# SwitchBoard_MP3_8.net
KiCad netlist of a schematic drawn in EAGLE
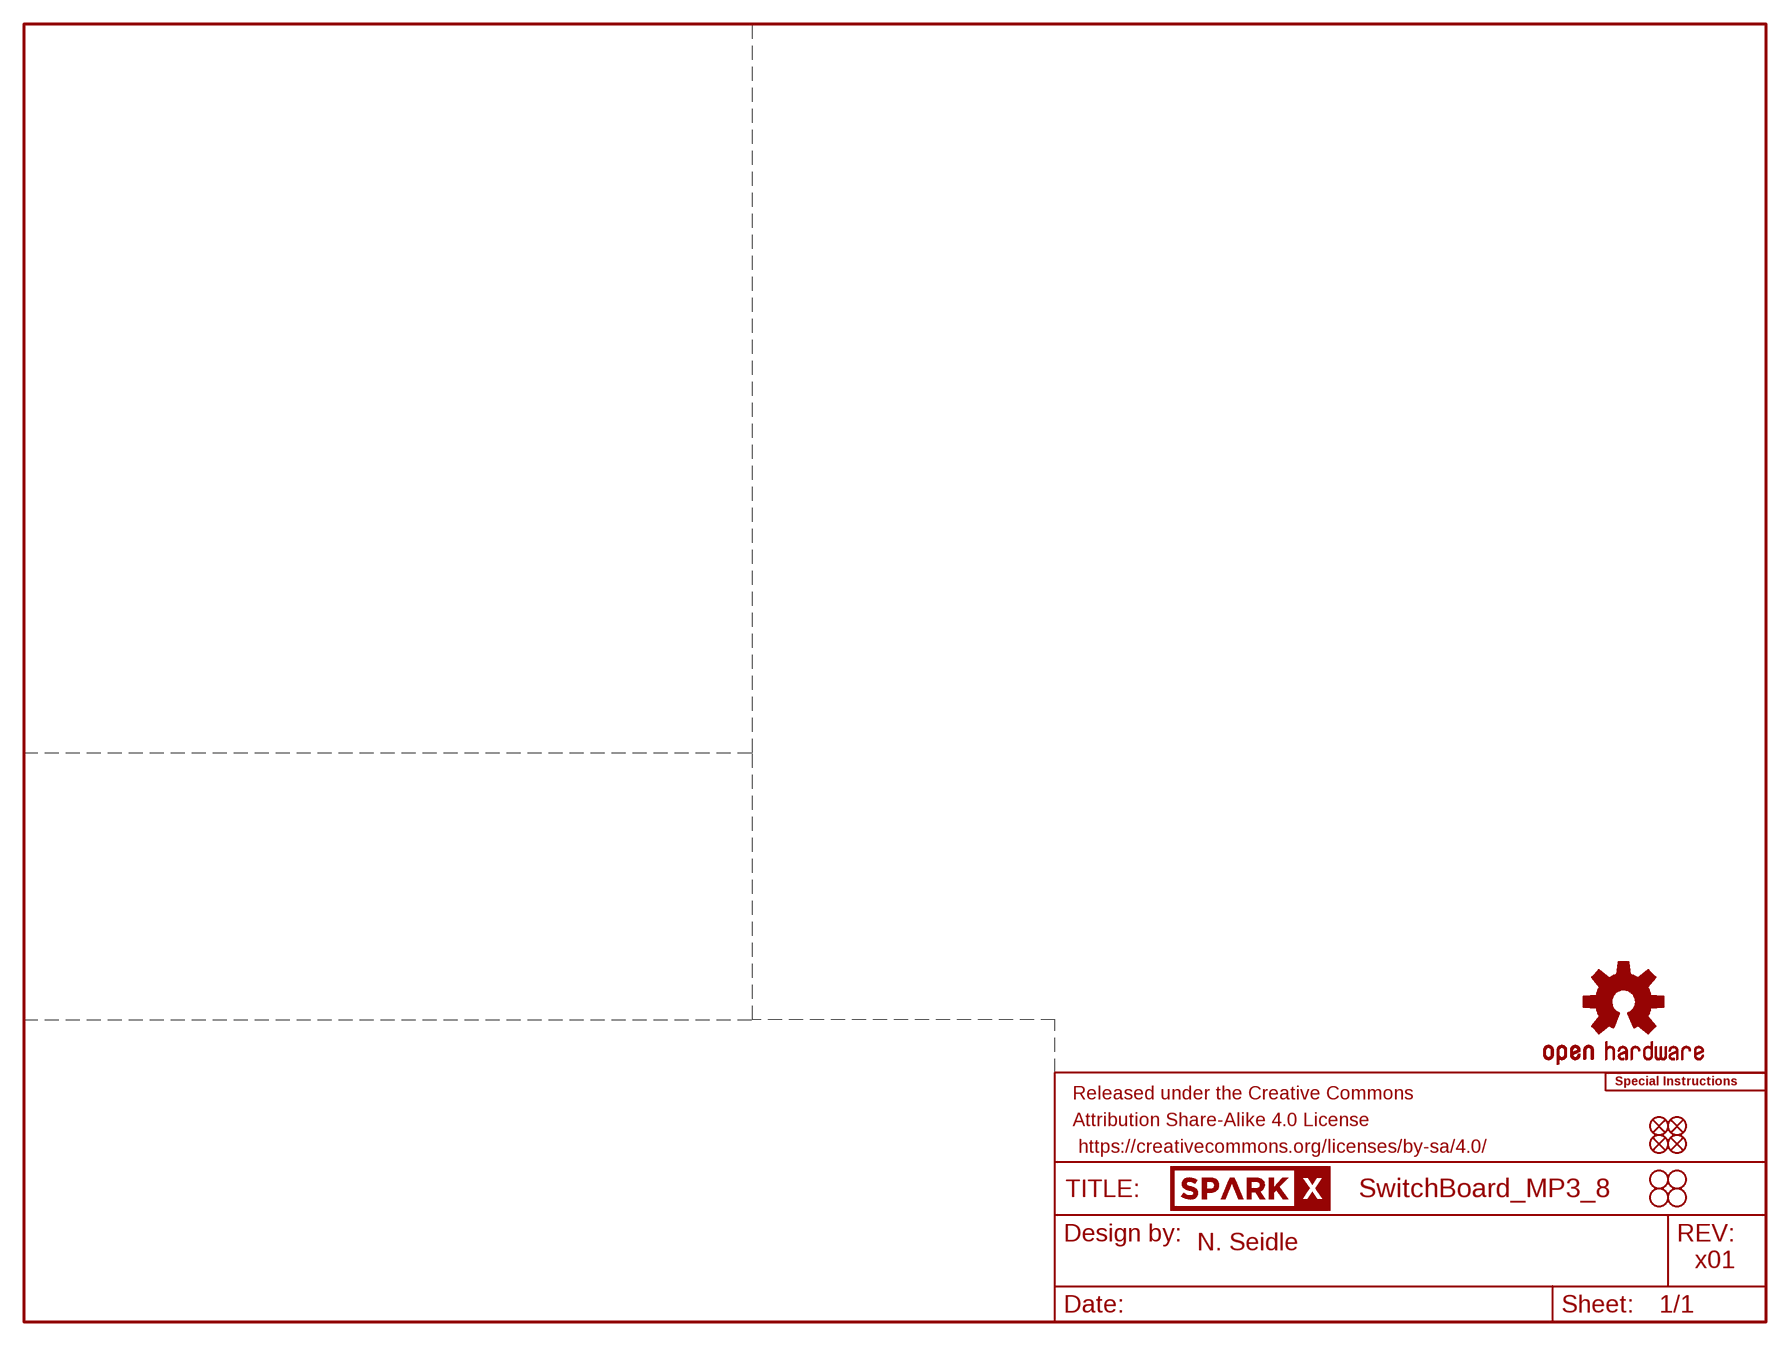
[diagram p0: schematic, sheet 1, part 1 of 2]
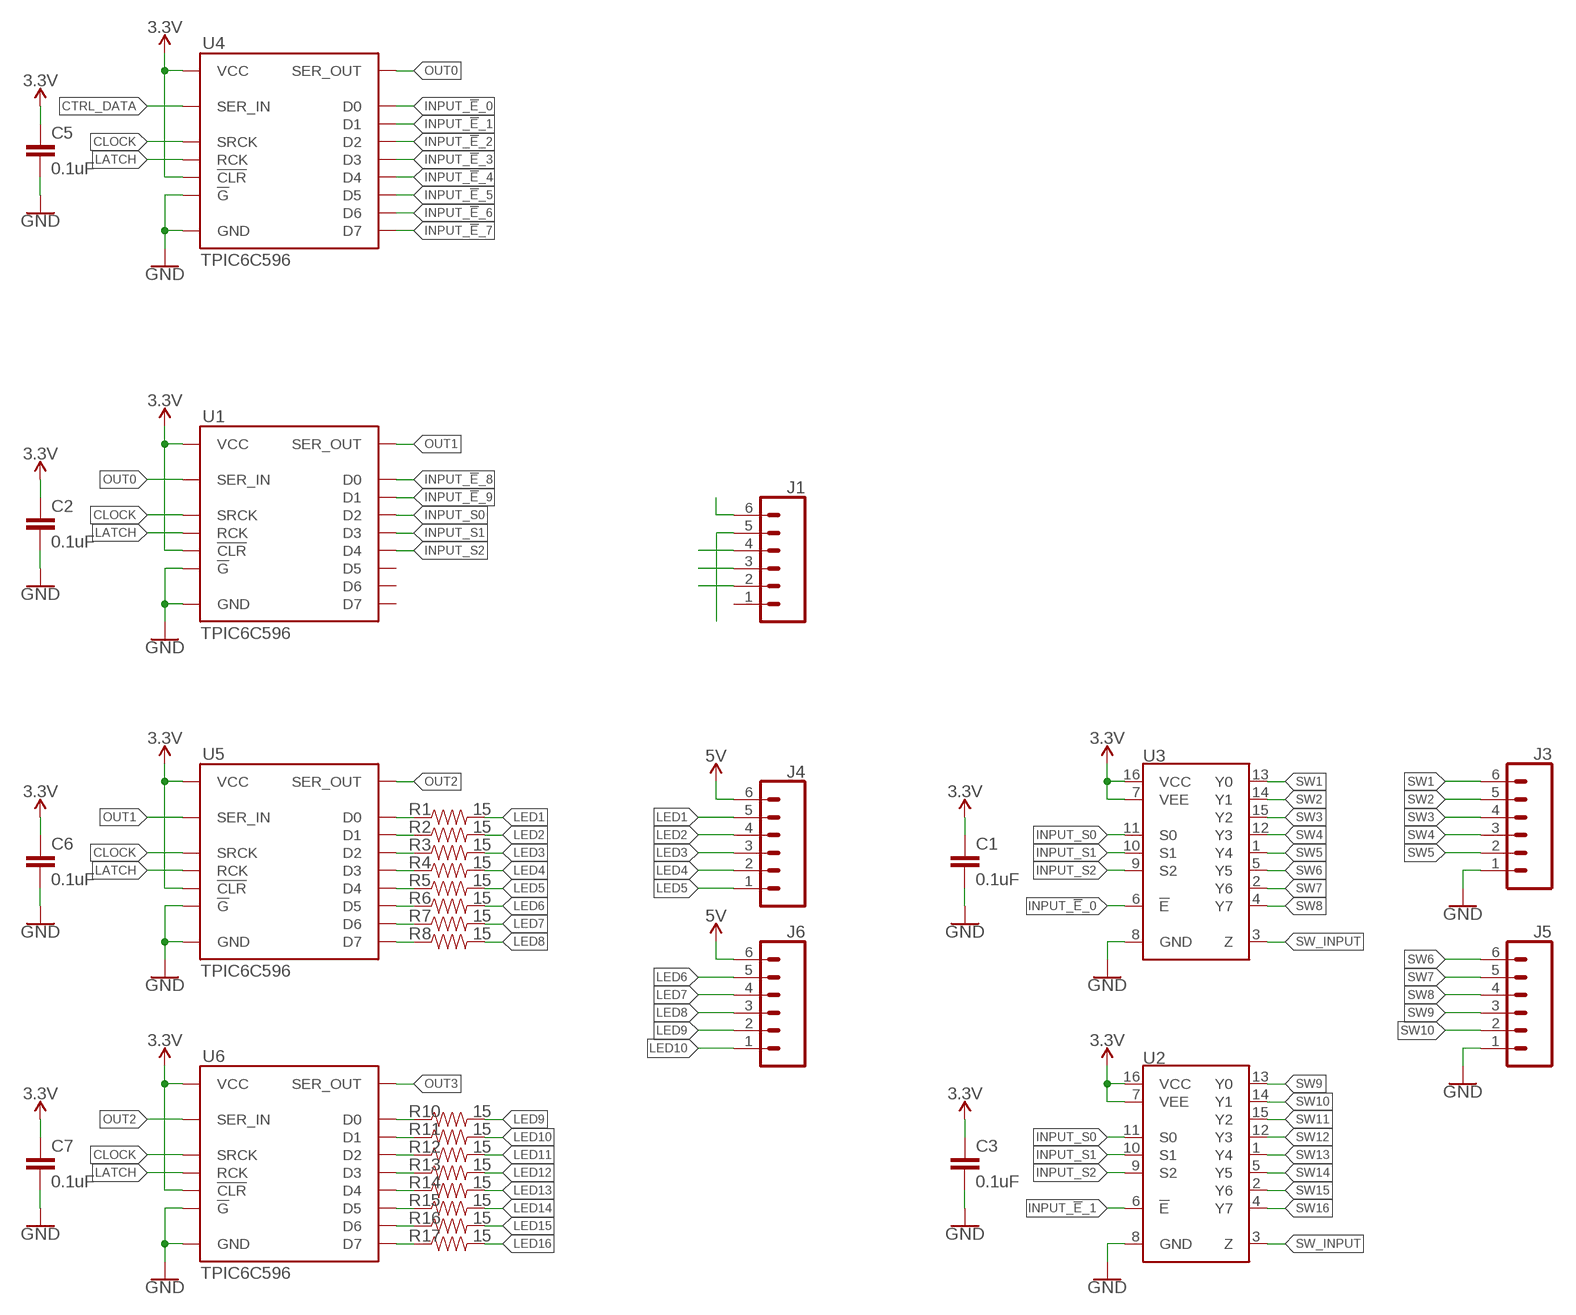
[diagram p1: schematic, sheet 1, part 2 of 2]

(export (version "E")
  (design (tool "Eeschema 10.0.6"))
  (components
    (comp (ref "C1")
      (value "0.1uF")
      (footprint "eagle-import:0603")
      (libsource (lib "eagle-import") (part "0.1UF-0603-25V-10%-X7R-WE"))
    )
    (comp (ref "C2")
      (value "0.1uF")
      (footprint "eagle-import:0603")
      (libsource (lib "eagle-import") (part "0.1UF-0603-25V-10%-X7R-WE"))
    )
    (comp (ref "C3")
      (value "0.1uF")
      (footprint "eagle-import:0603")
      (libsource (lib "eagle-import") (part "0.1UF-0603-25V-10%-X7R-WE"))
    )
    (comp (ref "C5")
      (value "0.1uF")
      (footprint "eagle-import:0603")
      (libsource (lib "eagle-import") (part "0.1UF-0603-25V-10%-X7R-WE"))
    )
    (comp (ref "C6")
      (value "0.1uF")
      (footprint "eagle-import:0603")
      (libsource (lib "eagle-import") (part "0.1UF-0603-25V-10%-X7R-WE"))
    )
    (comp (ref "C7")
      (value "0.1uF")
      (footprint "eagle-import:0603")
      (libsource (lib "eagle-import") (part "0.1UF-0603-25V-10%-X7R-WE"))
    )
    (comp (ref "FD1")
      (value "FIDUCIAL1X2")
      (footprint "eagle-import:FIDUCIAL-1X2")
      (libsource (lib "eagle-import") (part "FIDUCIAL1X2"))
    )
    (comp (ref "FD2")
      (value "FIDUCIAL1X2")
      (footprint "eagle-import:FIDUCIAL-1X2")
      (libsource (lib "eagle-import") (part "FIDUCIAL1X2"))
    )
    (comp (ref "FD3")
      (value "FIDUCIAL1X2")
      (footprint "eagle-import:FIDUCIAL-1X2")
      (libsource (lib "eagle-import") (part "FIDUCIAL1X2"))
    )
    (comp (ref "FD4")
      (value "FIDUCIAL1X2")
      (footprint "eagle-import:FIDUCIAL-1X2")
      (libsource (lib "eagle-import") (part "FIDUCIAL1X2"))
    )
    (comp (ref "FRAME1")
      (value "FRAME-LETTER")
      (footprint "eagle-import:CREATIVE_COMMONS")
      (libsource (lib "eagle-import") (part "FRAME-LETTER"))
    )
    (comp (ref "H1")
      (value "STAND-OFF")
      (footprint "eagle-import:STAND-OFF")
      (libsource (lib "eagle-import") (part "STAND-OFF"))
    )
    (comp (ref "H2")
      (value "STAND-OFF")
      (footprint "eagle-import:STAND-OFF")
      (libsource (lib "eagle-import") (part "STAND-OFF"))
    )
    (comp (ref "H3")
      (value "STAND-OFF")
      (footprint "eagle-import:STAND-OFF")
      (libsource (lib "eagle-import") (part "STAND-OFF"))
    )
    (comp (ref "H4")
      (value "STAND-OFF")
      (footprint "eagle-import:STAND-OFF")
      (libsource (lib "eagle-import") (part "STAND-OFF"))
    )
    (comp (ref "J1")
      (value "CONN_06JST-SMD-LOCKING")
      (footprint "eagle-import:JST-6-SMD-1.25MM-LOCKING")
      (libsource (lib "eagle-import") (part "CONN_06JST-SMD-LOCKING"))
    )
    (comp (ref "J3")
      (value "CONN_06JST-SMD-LOCKING")
      (footprint "eagle-import:JST-6-SMD-1.25MM-LOCKING")
      (libsource (lib "eagle-import") (part "CONN_06JST-SMD-LOCKING"))
    )
    (comp (ref "J4")
      (value "CONN_06JST-SMD-LOCKING")
      (footprint "eagle-import:JST-6-SMD-1.25MM-LOCKING")
      (libsource (lib "eagle-import") (part "CONN_06JST-SMD-LOCKING"))
    )
    (comp (ref "J5")
      (value "CONN_06JST-SMD-LOCKING")
      (footprint "eagle-import:JST-6-SMD-1.25MM-LOCKING")
      (libsource (lib "eagle-import") (part "CONN_06JST-SMD-LOCKING"))
    )
    (comp (ref "J6")
      (value "CONN_06JST-SMD-LOCKING")
      (footprint "eagle-import:JST-6-SMD-1.25MM-LOCKING")
      (libsource (lib "eagle-import") (part "CONN_06JST-SMD-LOCKING"))
    )
    (comp (ref "LOGO1")
      (value "SPECIAL_INSTRUCTIONS-ORDERING")
      (footprint "eagle-import:ORDERING_INSTRUCTIONS")
      (libsource (lib "eagle-import") (part "SPECIAL_INSTRUCTIONS-ORDERING"))
    )
    (comp (ref "LOGO2")
      (value "OSHW-LOGOS")
      (footprint "eagle-import:OSHW-LOGO-S")
      (libsource (lib "eagle-import") (part "OSHW-LOGOS"))
    )
    (comp (ref "R1")
      (value "15")
      (footprint "eagle-import:0603")
      (libsource (lib "eagle-import") (part "15OHM-0603-1/10W-1%"))
    )
    (comp (ref "R2")
      (value "15")
      (footprint "eagle-import:0603")
      (libsource (lib "eagle-import") (part "15OHM-0603-1/10W-1%"))
    )
    (comp (ref "R3")
      (value "15")
      (footprint "eagle-import:0603")
      (libsource (lib "eagle-import") (part "15OHM-0603-1/10W-1%"))
    )
    (comp (ref "R4")
      (value "15")
      (footprint "eagle-import:0603")
      (libsource (lib "eagle-import") (part "15OHM-0603-1/10W-1%"))
    )
    (comp (ref "R5")
      (value "15")
      (footprint "eagle-import:0603")
      (libsource (lib "eagle-import") (part "15OHM-0603-1/10W-1%"))
    )
    (comp (ref "R6")
      (value "15")
      (footprint "eagle-import:0603")
      (libsource (lib "eagle-import") (part "15OHM-0603-1/10W-1%"))
    )
    (comp (ref "R7")
      (value "15")
      (footprint "eagle-import:0603")
      (libsource (lib "eagle-import") (part "15OHM-0603-1/10W-1%"))
    )
    (comp (ref "R8")
      (value "15")
      (footprint "eagle-import:0603")
      (libsource (lib "eagle-import") (part "15OHM-0603-1/10W-1%"))
    )
    (comp (ref "R10")
      (value "15")
      (footprint "eagle-import:0603")
      (libsource (lib "eagle-import") (part "15OHM-0603-1/10W-1%"))
    )
    (comp (ref "R11")
      (value "15")
      (footprint "eagle-import:0603")
      (libsource (lib "eagle-import") (part "15OHM-0603-1/10W-1%"))
    )
    (comp (ref "R12")
      (value "15")
      (footprint "eagle-import:0603")
      (libsource (lib "eagle-import") (part "15OHM-0603-1/10W-1%"))
    )
    (comp (ref "R13")
      (value "15")
      (footprint "eagle-import:0603")
      (libsource (lib "eagle-import") (part "15OHM-0603-1/10W-1%"))
    )
    (comp (ref "R14")
      (value "15")
      (footprint "eagle-import:0603")
      (libsource (lib "eagle-import") (part "15OHM-0603-1/10W-1%"))
    )
    (comp (ref "R15")
      (value "15")
      (footprint "eagle-import:0603")
      (libsource (lib "eagle-import") (part "15OHM-0603-1/10W-1%"))
    )
    (comp (ref "R16")
      (value "15")
      (footprint "eagle-import:0603")
      (libsource (lib "eagle-import") (part "15OHM-0603-1/10W-1%"))
    )
    (comp (ref "R17")
      (value "15")
      (footprint "eagle-import:0603")
      (libsource (lib "eagle-import") (part "15OHM-0603-1/10W-1%"))
    )
    (comp (ref "U$1")
      (value "SPARKX-LOGO4")
      (footprint "eagle-import:SPARKX-MEDIUM")
      (libsource (lib "eagle-import") (part "SPARKX-LOGO4"))
    )
    (comp (ref "U1")
      (value "TPIC6C596")
      (footprint "eagle-import:SO016")
      (libsource (lib "eagle-import") (part "TPIC6C596SOIC"))
    )
    (comp (ref "U2")
      (value "744051")
      (footprint "eagle-import:SO16")
      (libsource (lib "eagle-import") (part "744051"))
    )
    (comp (ref "U3")
      (value "744051")
      (footprint "eagle-import:SO16")
      (libsource (lib "eagle-import") (part "744051"))
    )
    (comp (ref "U4")
      (value "TPIC6C596")
      (footprint "eagle-import:SO016")
      (libsource (lib "eagle-import") (part "TPIC6C596SOIC"))
    )
    (comp (ref "U5")
      (value "TPIC6C596")
      (footprint "eagle-import:SO016")
      (libsource (lib "eagle-import") (part "TPIC6C596SOIC"))
    )
    (comp (ref "U6")
      (value "TPIC6C596")
      (footprint "eagle-import:SO016")
      (libsource (lib "eagle-import") (part "TPIC6C596SOIC"))
    )
  )
  (nets
    (net (code "1") (name "/INPUT_~{E}_0") (class "Default")
      (node (ref "U3") (pin "6") (pinfunction "~{E}_6") (pintype "bidirectional"))
      (node (ref "U4") (pin "3") (pinfunction "D0_3") (pintype "output"))
    )
    (net (code "2") (name "/INPUT_~{E}_1") (class "Default")
      (node (ref "U2") (pin "6") (pinfunction "~{E}_6") (pintype "bidirectional"))
      (node (ref "U4") (pin "4") (pinfunction "D1_4") (pintype "output"))
    )
    (net (code "3") (name "/INPUT_~{E}_2") (class "Default")
      (node (ref "U4") (pin "5") (pinfunction "D2_5") (pintype "output"))
    )
    (net (code "4") (name "/INPUT_~{E}_3") (class "Default")
      (node (ref "U4") (pin "6") (pinfunction "D3_6") (pintype "output"))
    )
    (net (code "5") (name "/INPUT_~{E}_4") (class "Default")
      (node (ref "U4") (pin "11") (pinfunction "D4_11") (pintype "output"))
    )
    (net (code "6") (name "/INPUT_~{E}_5") (class "Default")
      (node (ref "U4") (pin "12") (pinfunction "D5_12") (pintype "output"))
    )
    (net (code "7") (name "/INPUT_~{E}_6") (class "Default")
      (node (ref "U4") (pin "13") (pinfunction "D6_13") (pintype "output"))
    )
    (net (code "8") (name "/INPUT_~{E}_7") (class "Default")
      (node (ref "U4") (pin "14") (pinfunction "D7_14") (pintype "output"))
    )
    (net (code "9") (name "/INPUT_~{E}_8") (class "Default")
      (node (ref "U1") (pin "3") (pinfunction "D0_3") (pintype "output"))
    )
    (net (code "10") (name "/INPUT_~{E}_9") (class "Default")
      (node (ref "U1") (pin "4") (pinfunction "D1_4") (pintype "output"))
    )
    (net (code "11") (name "3.3V") (class "Default")
      (node (ref "C1") (pin "1") (pinfunction "1_1") (pintype "passive"))
      (node (ref "C2") (pin "1") (pinfunction "1_1") (pintype "passive"))
      (node (ref "C3") (pin "1") (pinfunction "1_1") (pintype "passive"))
      (node (ref "C5") (pin "1") (pinfunction "1_1") (pintype "passive"))
      (node (ref "C6") (pin "1") (pinfunction "1_1") (pintype "passive"))
      (node (ref "C7") (pin "1") (pinfunction "1_1") (pintype "passive"))
      (node (ref "U1") (pin "1") (pinfunction "VCC_1") (pintype "power_in"))
      (node (ref "U1") (pin "7") (pinfunction "~{CLR}_7") (pintype "input"))
      (node (ref "U2") (pin "16") (pinfunction "VCC_16") (pintype "bidirectional"))
      (node (ref "U2") (pin "7") (pinfunction "VEE_7") (pintype "bidirectional"))
      (node (ref "U3") (pin "16") (pinfunction "VCC_16") (pintype "bidirectional"))
      (node (ref "U3") (pin "7") (pinfunction "VEE_7") (pintype "bidirectional"))
      (node (ref "U4") (pin "1") (pinfunction "VCC_1") (pintype "power_in"))
      (node (ref "U4") (pin "7") (pinfunction "~{CLR}_7") (pintype "input"))
      (node (ref "U5") (pin "1") (pinfunction "VCC_1") (pintype "power_in"))
      (node (ref "U5") (pin "7") (pinfunction "~{CLR}_7") (pintype "input"))
      (node (ref "U6") (pin "1") (pinfunction "VCC_1") (pintype "power_in"))
      (node (ref "U6") (pin "7") (pinfunction "~{CLR}_7") (pintype "input"))
    )
    (net (code "12") (name "5V") (class "Default")
      (node (ref "J4") (pin "6") (pinfunction "6_6") (pintype "passive"))
      (node (ref "J6") (pin "6") (pinfunction "6_6") (pintype "passive"))
    )
    (net (code "13") (name "CLOCK") (class "Default")
      (node (ref "U1") (pin "15") (pinfunction "SRCK_15") (pintype "input"))
      (node (ref "U4") (pin "15") (pinfunction "SRCK_15") (pintype "input"))
      (node (ref "U5") (pin "15") (pinfunction "SRCK_15") (pintype "input"))
      (node (ref "U6") (pin "15") (pinfunction "SRCK_15") (pintype "input"))
    )
    (net (code "14") (name "CTRL_DATA") (class "Default")
      (node (ref "U4") (pin "2") (pinfunction "SER_IN_2") (pintype "input"))
    )
    (net (code "15") (name "GND") (class "Default")
      (node (ref "C1") (pin "2") (pinfunction "2_2") (pintype "passive"))
      (node (ref "C2") (pin "2") (pinfunction "2_2") (pintype "passive"))
      (node (ref "C3") (pin "2") (pinfunction "2_2") (pintype "passive"))
      (node (ref "C5") (pin "2") (pinfunction "2_2") (pintype "passive"))
      (node (ref "C6") (pin "2") (pinfunction "2_2") (pintype "passive"))
      (node (ref "C7") (pin "2") (pinfunction "2_2") (pintype "passive"))
      (node (ref "J3") (pin "1") (pinfunction "1_1") (pintype "passive"))
      (node (ref "J5") (pin "1") (pinfunction "1_1") (pintype "passive"))
      (node (ref "U1") (pin "16") (pinfunction "GND_16") (pintype "power_in"))
      (node (ref "U1") (pin "8") (pinfunction "~{G}_8") (pintype "input"))
      (node (ref "U2") (pin "8") (pinfunction "GND_8") (pintype "bidirectional"))
      (node (ref "U3") (pin "8") (pinfunction "GND_8") (pintype "bidirectional"))
      (node (ref "U4") (pin "16") (pinfunction "GND_16") (pintype "power_in"))
      (node (ref "U4") (pin "8") (pinfunction "~{G}_8") (pintype "input"))
      (node (ref "U5") (pin "16") (pinfunction "GND_16") (pintype "power_in"))
      (node (ref "U5") (pin "8") (pinfunction "~{G}_8") (pintype "input"))
      (node (ref "U6") (pin "16") (pinfunction "GND_16") (pintype "power_in"))
      (node (ref "U6") (pin "8") (pinfunction "~{G}_8") (pintype "input"))
    )
    (net (code "16") (name "INPUT_S0") (class "Default")
      (node (ref "U1") (pin "5") (pinfunction "D2_5") (pintype "output"))
      (node (ref "U2") (pin "11") (pinfunction "S0_11") (pintype "bidirectional"))
      (node (ref "U3") (pin "11") (pinfunction "S0_11") (pintype "bidirectional"))
    )
    (net (code "17") (name "INPUT_S1") (class "Default")
      (node (ref "U1") (pin "6") (pinfunction "D3_6") (pintype "output"))
      (node (ref "U2") (pin "10") (pinfunction "S1_10") (pintype "bidirectional"))
      (node (ref "U3") (pin "10") (pinfunction "S1_10") (pintype "bidirectional"))
    )
    (net (code "18") (name "INPUT_S2") (class "Default")
      (node (ref "U1") (pin "11") (pinfunction "D4_11") (pintype "output"))
      (node (ref "U2") (pin "9") (pinfunction "S2_9") (pintype "bidirectional"))
      (node (ref "U3") (pin "9") (pinfunction "S2_9") (pintype "bidirectional"))
    )
    (net (code "19") (name "LATCH") (class "Default")
      (node (ref "U1") (pin "10") (pinfunction "RCK_10") (pintype "input"))
      (node (ref "U4") (pin "10") (pinfunction "RCK_10") (pintype "input"))
      (node (ref "U5") (pin "10") (pinfunction "RCK_10") (pintype "input"))
      (node (ref "U6") (pin "10") (pinfunction "RCK_10") (pintype "input"))
    )
    (net (code "20") (name "LED1") (class "Default")
      (node (ref "J4") (pin "5") (pinfunction "5_5") (pintype "passive"))
      (node (ref "R1") (pin "2") (pinfunction "2_2") (pintype "passive"))
    )
    (net (code "21") (name "LED2") (class "Default")
      (node (ref "J4") (pin "4") (pinfunction "4_4") (pintype "passive"))
      (node (ref "R2") (pin "2") (pinfunction "2_2") (pintype "passive"))
    )
    (net (code "22") (name "LED3") (class "Default")
      (node (ref "J4") (pin "3") (pinfunction "3_3") (pintype "passive"))
      (node (ref "R3") (pin "2") (pinfunction "2_2") (pintype "passive"))
    )
    (net (code "23") (name "LED4") (class "Default")
      (node (ref "J4") (pin "2") (pinfunction "2_2") (pintype "passive"))
      (node (ref "R4") (pin "2") (pinfunction "2_2") (pintype "passive"))
    )
    (net (code "24") (name "LED5") (class "Default")
      (node (ref "J4") (pin "1") (pinfunction "1_1") (pintype "passive"))
      (node (ref "R5") (pin "2") (pinfunction "2_2") (pintype "passive"))
    )
    (net (code "25") (name "LED6") (class "Default")
      (node (ref "J6") (pin "5") (pinfunction "5_5") (pintype "passive"))
      (node (ref "R6") (pin "2") (pinfunction "2_2") (pintype "passive"))
    )
    (net (code "26") (name "LED7") (class "Default")
      (node (ref "J6") (pin "4") (pinfunction "4_4") (pintype "passive"))
      (node (ref "R7") (pin "2") (pinfunction "2_2") (pintype "passive"))
    )
    (net (code "27") (name "LED8") (class "Default")
      (node (ref "J6") (pin "3") (pinfunction "3_3") (pintype "passive"))
      (node (ref "R8") (pin "2") (pinfunction "2_2") (pintype "passive"))
    )
    (net (code "28") (name "LED9") (class "Default")
      (node (ref "J6") (pin "2") (pinfunction "2_2") (pintype "passive"))
      (node (ref "R10") (pin "2") (pinfunction "2_2") (pintype "passive"))
    )
    (net (code "29") (name "LED10") (class "Default")
      (node (ref "J6") (pin "1") (pinfunction "1_1") (pintype "passive"))
      (node (ref "R11") (pin "2") (pinfunction "2_2") (pintype "passive"))
    )
    (net (code "30") (name "LED11") (class "Default")
      (node (ref "R12") (pin "2") (pinfunction "2_2") (pintype "passive"))
    )
    (net (code "31") (name "LED12") (class "Default")
      (node (ref "R13") (pin "2") (pinfunction "2_2") (pintype "passive"))
    )
    (net (code "32") (name "LED13") (class "Default")
      (node (ref "R14") (pin "2") (pinfunction "2_2") (pintype "passive"))
    )
    (net (code "33") (name "LED14") (class "Default")
      (node (ref "R15") (pin "2") (pinfunction "2_2") (pintype "passive"))
    )
    (net (code "34") (name "LED15") (class "Default")
      (node (ref "R16") (pin "2") (pinfunction "2_2") (pintype "passive"))
    )
    (net (code "35") (name "LED16") (class "Default")
      (node (ref "R17") (pin "2") (pinfunction "2_2") (pintype "passive"))
    )
    (net (code "36") (name "Net-(U5-D0)") (class "Default")
      (node (ref "R1") (pin "1") (pinfunction "1_1") (pintype "passive"))
      (node (ref "U5") (pin "3") (pinfunction "D0_3") (pintype "output"))
    )
    (net (code "37") (name "Net-(U5-D1)") (class "Default")
      (node (ref "R2") (pin "1") (pinfunction "1_1") (pintype "passive"))
      (node (ref "U5") (pin "4") (pinfunction "D1_4") (pintype "output"))
    )
    (net (code "38") (name "Net-(U5-D2)") (class "Default")
      (node (ref "R3") (pin "1") (pinfunction "1_1") (pintype "passive"))
      (node (ref "U5") (pin "5") (pinfunction "D2_5") (pintype "output"))
    )
    (net (code "39") (name "Net-(U5-D3)") (class "Default")
      (node (ref "R4") (pin "1") (pinfunction "1_1") (pintype "passive"))
      (node (ref "U5") (pin "6") (pinfunction "D3_6") (pintype "output"))
    )
    (net (code "40") (name "Net-(U5-D4)") (class "Default")
      (node (ref "R5") (pin "1") (pinfunction "1_1") (pintype "passive"))
      (node (ref "U5") (pin "11") (pinfunction "D4_11") (pintype "output"))
    )
    (net (code "41") (name "Net-(U5-D5)") (class "Default")
      (node (ref "R6") (pin "1") (pinfunction "1_1") (pintype "passive"))
      (node (ref "U5") (pin "12") (pinfunction "D5_12") (pintype "output"))
    )
    (net (code "42") (name "Net-(U5-D6)") (class "Default")
      (node (ref "R7") (pin "1") (pinfunction "1_1") (pintype "passive"))
      (node (ref "U5") (pin "13") (pinfunction "D6_13") (pintype "output"))
    )
    (net (code "43") (name "Net-(U5-D7)") (class "Default")
      (node (ref "R8") (pin "1") (pinfunction "1_1") (pintype "passive"))
      (node (ref "U5") (pin "14") (pinfunction "D7_14") (pintype "output"))
    )
    (net (code "44") (name "Net-(U6-D0)") (class "Default")
      (node (ref "R10") (pin "1") (pinfunction "1_1") (pintype "passive"))
      (node (ref "U6") (pin "3") (pinfunction "D0_3") (pintype "output"))
    )
    (net (code "45") (name "Net-(U6-D1)") (class "Default")
      (node (ref "R11") (pin "1") (pinfunction "1_1") (pintype "passive"))
      (node (ref "U6") (pin "4") (pinfunction "D1_4") (pintype "output"))
    )
    (net (code "46") (name "Net-(U6-D2)") (class "Default")
      (node (ref "R12") (pin "1") (pinfunction "1_1") (pintype "passive"))
      (node (ref "U6") (pin "5") (pinfunction "D2_5") (pintype "output"))
    )
    (net (code "47") (name "Net-(U6-D3)") (class "Default")
      (node (ref "R13") (pin "1") (pinfunction "1_1") (pintype "passive"))
      (node (ref "U6") (pin "6") (pinfunction "D3_6") (pintype "output"))
    )
    (net (code "48") (name "Net-(U6-D4)") (class "Default")
      (node (ref "R14") (pin "1") (pinfunction "1_1") (pintype "passive"))
      (node (ref "U6") (pin "11") (pinfunction "D4_11") (pintype "output"))
    )
    (net (code "49") (name "Net-(U6-D5)") (class "Default")
      (node (ref "R15") (pin "1") (pinfunction "1_1") (pintype "passive"))
      (node (ref "U6") (pin "12") (pinfunction "D5_12") (pintype "output"))
    )
    (net (code "50") (name "Net-(U6-D6)") (class "Default")
      (node (ref "R16") (pin "1") (pinfunction "1_1") (pintype "passive"))
      (node (ref "U6") (pin "13") (pinfunction "D6_13") (pintype "output"))
    )
    (net (code "51") (name "Net-(U6-D7)") (class "Default")
      (node (ref "R17") (pin "1") (pinfunction "1_1") (pintype "passive"))
      (node (ref "U6") (pin "14") (pinfunction "D7_14") (pintype "output"))
    )
    (net (code "52") (name "OUT0") (class "Default")
      (node (ref "U1") (pin "2") (pinfunction "SER_IN_2") (pintype "input"))
      (node (ref "U4") (pin "9") (pinfunction "SER_OUT_9") (pintype "output"))
    )
    (net (code "53") (name "OUT1") (class "Default")
      (node (ref "U1") (pin "9") (pinfunction "SER_OUT_9") (pintype "output"))
      (node (ref "U5") (pin "2") (pinfunction "SER_IN_2") (pintype "input"))
    )
    (net (code "54") (name "OUT2") (class "Default")
      (node (ref "U5") (pin "9") (pinfunction "SER_OUT_9") (pintype "output"))
      (node (ref "U6") (pin "2") (pinfunction "SER_IN_2") (pintype "input"))
    )
    (net (code "55") (name "OUT3") (class "Default")
      (node (ref "U6") (pin "9") (pinfunction "SER_OUT_9") (pintype "output"))
    )
    (net (code "56") (name "SW1") (class "Default")
      (node (ref "J3") (pin "6") (pinfunction "6_6") (pintype "passive"))
      (node (ref "U3") (pin "13") (pinfunction "Y0_13") (pintype "bidirectional"))
    )
    (net (code "57") (name "SW2") (class "Default")
      (node (ref "J3") (pin "5") (pinfunction "5_5") (pintype "passive"))
      (node (ref "U3") (pin "14") (pinfunction "Y1_14") (pintype "bidirectional"))
    )
    (net (code "58") (name "SW3") (class "Default")
      (node (ref "J3") (pin "4") (pinfunction "4_4") (pintype "passive"))
      (node (ref "U3") (pin "15") (pinfunction "Y2_15") (pintype "bidirectional"))
    )
    (net (code "59") (name "SW4") (class "Default")
      (node (ref "J3") (pin "3") (pinfunction "3_3") (pintype "passive"))
      (node (ref "U3") (pin "12") (pinfunction "Y3_12") (pintype "bidirectional"))
    )
    (net (code "60") (name "SW5") (class "Default")
      (node (ref "J3") (pin "2") (pinfunction "2_2") (pintype "passive"))
      (node (ref "U3") (pin "1") (pinfunction "Y4_1") (pintype "bidirectional"))
    )
    (net (code "61") (name "SW6") (class "Default")
      (node (ref "J5") (pin "6") (pinfunction "6_6") (pintype "passive"))
      (node (ref "U3") (pin "5") (pinfunction "Y5_5") (pintype "bidirectional"))
    )
    (net (code "62") (name "SW7") (class "Default")
      (node (ref "J5") (pin "5") (pinfunction "5_5") (pintype "passive"))
      (node (ref "U3") (pin "2") (pinfunction "Y6_2") (pintype "bidirectional"))
    )
    (net (code "63") (name "SW8") (class "Default")
      (node (ref "J5") (pin "4") (pinfunction "4_4") (pintype "passive"))
      (node (ref "U3") (pin "4") (pinfunction "Y7_4") (pintype "bidirectional"))
    )
    (net (code "64") (name "SW9") (class "Default")
      (node (ref "J5") (pin "3") (pinfunction "3_3") (pintype "passive"))
      (node (ref "U2") (pin "13") (pinfunction "Y0_13") (pintype "bidirectional"))
    )
    (net (code "65") (name "SW10") (class "Default")
      (node (ref "J5") (pin "2") (pinfunction "2_2") (pintype "passive"))
      (node (ref "U2") (pin "14") (pinfunction "Y1_14") (pintype "bidirectional"))
    )
    (net (code "66") (name "SW11") (class "Default")
      (node (ref "U2") (pin "15") (pinfunction "Y2_15") (pintype "bidirectional"))
    )
    (net (code "67") (name "SW12") (class "Default")
      (node (ref "U2") (pin "12") (pinfunction "Y3_12") (pintype "bidirectional"))
    )
    (net (code "68") (name "SW13") (class "Default")
      (node (ref "U2") (pin "1") (pinfunction "Y4_1") (pintype "bidirectional"))
    )
    (net (code "69") (name "SW14") (class "Default")
      (node (ref "U2") (pin "5") (pinfunction "Y5_5") (pintype "bidirectional"))
    )
    (net (code "70") (name "SW15") (class "Default")
      (node (ref "U2") (pin "2") (pinfunction "Y6_2") (pintype "bidirectional"))
    )
    (net (code "71") (name "SW16") (class "Default")
      (node (ref "U2") (pin "4") (pinfunction "Y7_4") (pintype "bidirectional"))
    )
    (net (code "72") (name "SW_INPUT") (class "Default")
      (node (ref "U2") (pin "3") (pinfunction "Z_3") (pintype "bidirectional"))
      (node (ref "U3") (pin "3") (pinfunction "Z_3") (pintype "bidirectional"))
    )
    (net (code "73") (name "unconnected-(J1-Pad1)") (class "Default")
      (node (ref "J1") (pin "1") (pinfunction "1_1") (pintype "passive"))
    )
    (net (code "74") (name "unconnected-(J1-Pad2)") (class "Default")
      (node (ref "J1") (pin "2") (pinfunction "2_2") (pintype "passive"))
    )
    (net (code "75") (name "unconnected-(J1-Pad3)") (class "Default")
      (node (ref "J1") (pin "3") (pinfunction "3_3") (pintype "passive"))
    )
    (net (code "76") (name "unconnected-(J1-Pad4)") (class "Default")
      (node (ref "J1") (pin "4") (pinfunction "4_4") (pintype "passive"))
    )
    (net (code "77") (name "unconnected-(J1-Pad5)") (class "Default")
      (node (ref "J1") (pin "5") (pinfunction "5_5") (pintype "passive"))
    )
    (net (code "78") (name "unconnected-(J1-Pad6)") (class "Default")
      (node (ref "J1") (pin "6") (pinfunction "6_6") (pintype "passive"))
    )
    (net (code "79") (name "unconnected-(U1-D5-Pad12)") (class "Default")
      (node (ref "U1") (pin "12") (pinfunction "D5_12") (pintype "output"))
    )
    (net (code "80") (name "unconnected-(U1-D6-Pad13)") (class "Default")
      (node (ref "U1") (pin "13") (pinfunction "D6_13") (pintype "output"))
    )
    (net (code "81") (name "unconnected-(U1-D7-Pad14)") (class "Default")
      (node (ref "U1") (pin "14") (pinfunction "D7_14") (pintype "output"))
    )
  )
)
